# CAN_SN65HVD233.net
KiCad netlist of a schematic drawn in Altium Designer
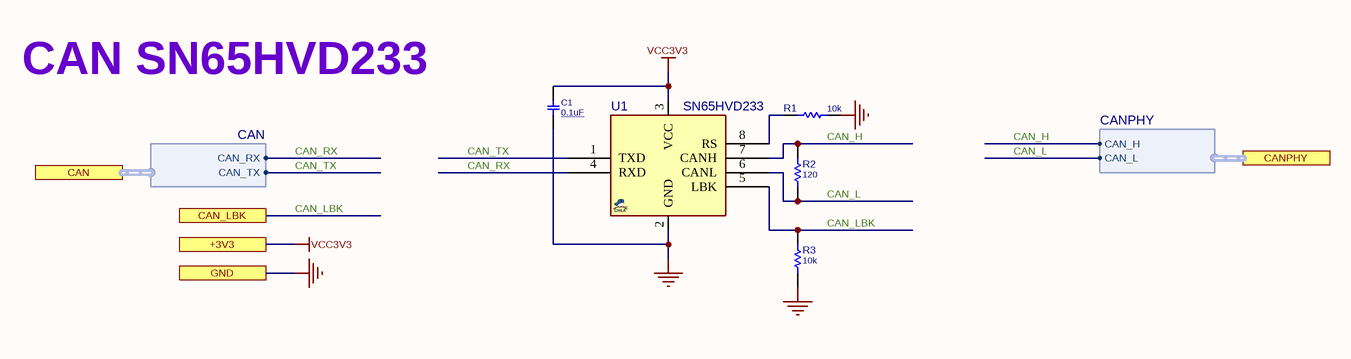
[diagram p0: CAN_SN65HVD233.SchDoc]

(export (version "E")
  (design (tool "Eeschema 10.0.6"))
  (components
    (comp (ref "C1")
      (value "0.1uF")
      (footprint "C0402")
      (description "CAP, MLCC")
      (fields (field (name "MANF_P#") "MANF_PART#"))
      (libsource (lib "passive_smd") (part "CAP_SMD_MLCC_0402"))
    )
    (comp (ref "R1")
      (value "10k")
      (footprint "R0402")
      (description "RESISTOR, SMD")
      (libsource (lib "passive_smd") (part "RES_SMD_0402"))
    )
    (comp (ref "R2")
      (value "120")
      (footprint "R0603")
      (description "RESISTOR, SMD")
      (libsource (lib "passive_smd") (part "RES_SMD_0402"))
    )
    (comp (ref "R3")
      (value "10k")
      (footprint "R0402")
      (description "RESISTOR, SMD")
      (libsource (lib "passive_smd") (part "RES_SMD_0402"))
    )
    (comp (ref "U1")
      (value "SN65HVD233")
      (footprint "SO_8")
      (description "CAN,  Transceivers, 3.3VCC")
      (fields (field (name "MANF") "Texas Instruments") (field (name "MANF_P#") "SN65HVD233D"))
      (libsource (lib "can_phy") (part "SN65HVD233_SOP8"))
    )
  )
  (nets
    (net (code "3") (name "/CAN_H") (class "Default")
      (node (ref "R2") (pin "2") (pinfunction "2_2") (pintype "passive"))
      (node (ref "U1") (pin "7") (pinfunction "CANH_7") (pintype "passive"))
    )
    (net (code "4") (name "/CAN_L") (class "Default")
      (node (ref "R2") (pin "1") (pinfunction "1_1") (pintype "passive"))
      (node (ref "U1") (pin "6") (pinfunction "CANL_6") (pintype "passive"))
    )
    (net (code "5") (name "/CAN_LBK") (class "Default")
      (node (ref "R3") (pin "2") (pinfunction "2_2") (pintype "passive"))
      (node (ref "U1") (pin "5") (pinfunction "LBK_5") (pintype "passive"))
    )
    (net (code "6") (name "/CAN_RX") (class "Default")
      (node (ref "U1") (pin "4") (pinfunction "RXD_4") (pintype "passive"))
    )
    (net (code "7") (name "/CAN_TX") (class "Default")
      (node (ref "U1") (pin "1") (pinfunction "TXD_1") (pintype "passive"))
    )
    (net (code "10") (name "GND") (class "Default")
      (node (ref "C1") (pin "1") (pinfunction "1_1") (pintype "passive"))
      (node (ref "R1") (pin "1") (pinfunction "1_1") (pintype "passive"))
      (node (ref "R3") (pin "1") (pinfunction "1_1") (pintype "passive"))
      (node (ref "U1") (pin "2") (pinfunction "GND_2") (pintype "passive"))
    )
    (net (code "11") (name "Net-(U1-RS)") (class "Default")
      (node (ref "R1") (pin "2") (pinfunction "2_2") (pintype "passive"))
      (node (ref "U1") (pin "8") (pinfunction "RS_8") (pintype "passive"))
    )
    (net (code "12") (name "VCC3V3") (class "Default")
      (node (ref "C1") (pin "2") (pinfunction "2_2") (pintype "passive"))
      (node (ref "U1") (pin "3") (pinfunction "VCC_3") (pintype "passive"))
    )
  )
)
